# USB_DVI.net
KiCad netlist of a schematic drawn in Altium Designer
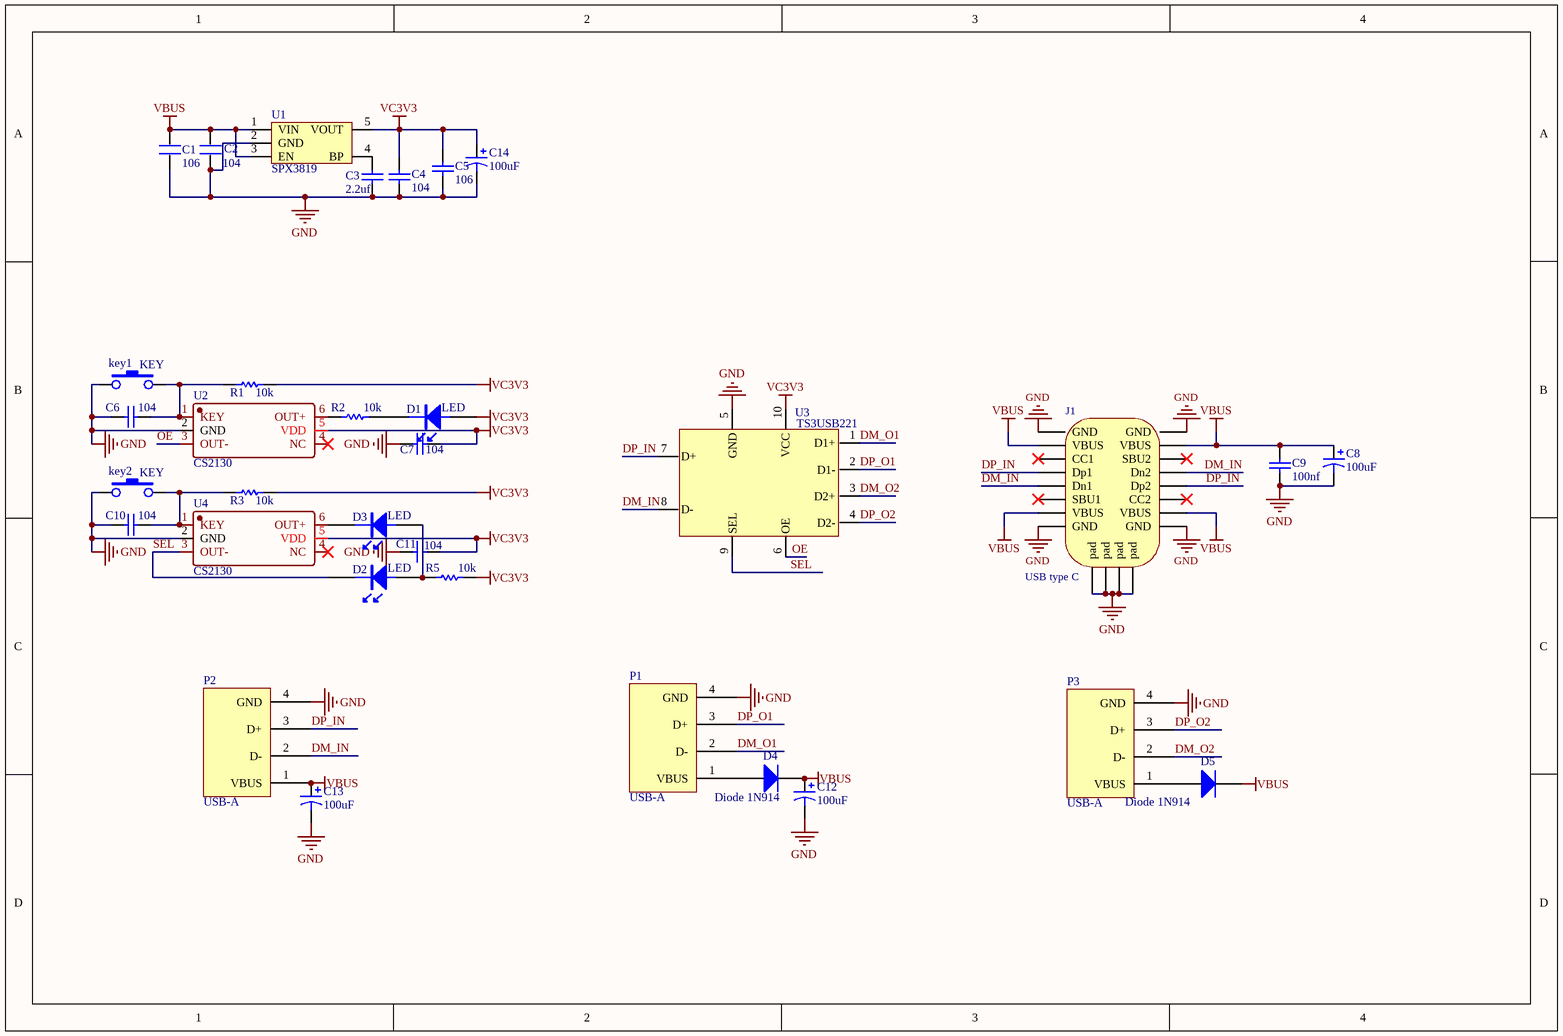
[diagram p0: USB_DVI.SchDoc]

(export (version "E")
  (design (tool "Eeschema 10.0.6"))
  (components
    (comp (ref "C1") (value "106") (footprint "C 0603") (libsource (lib "Mlia") (part "0603C")))
    (comp (ref "C2") (value "104") (footprint "C 0603") (libsource (lib "Mlia") (part "0603C")))
    (comp (ref "C3")
      (value "2.2uf")
      (footprint "C 0603")
      (description "Polarized Capacitor (Radial)")
      (fields (field (name "Comment") "Cap") (field (name "PUBLISHER") "Altium Limited"))
      (libsource (lib "Fantasy") (part "Cap"))
    )
    (comp (ref "C4")
      (value "104")
      (footprint "C 0603")
      (description "Polarized Capacitor (Radial)")
      (fields (field (name "Comment") "Cap") (field (name "PUBLISHER") "Altium Limited"))
      (libsource (lib "Fantasy") (part "Cap"))
    )
    (comp (ref "C5")
      (value "106")
      (footprint "C 0603")
      (description "Polarized Capacitor (Radial)")
      (fields (field (name "Comment") "Cap") (field (name "PUBLISHER") "Altium Limited"))
      (libsource (lib "Fantasy") (part "Cap"))
    )
    (comp (ref "C6")
      (value "104")
      (footprint "C 0603")
      (description "Polarized Capacitor (Radial)")
      (fields (field (name "Comment") "Cap") (field (name "PUBLISHER") "Altium Limited"))
      (libsource (lib "Fantasy") (part "Cap"))
    )
    (comp (ref "C7")
      (value "104")
      (footprint "C 0603")
      (description "Polarized Capacitor (Radial)")
      (fields (field (name "Comment") "Cap") (field (name "PUBLISHER") "Altium Limited"))
      (libsource (lib "Fantasy") (part "Cap"))
    )
    (comp (ref "C8")
      (value "100uF")
      (footprint "C 1210")
      (description "贴片电解电容")
      (fields (field (name "PUBLISHER") "Altium Limited"))
      (libsource (lib "Miscellaneous Devices") (part "Cap Pol1"))
    )
    (comp (ref "C9")
      (value "100nf")
      (footprint "C 0603")
      (description "贴片电容")
      (fields (field (name "PUBLISHER") "Altium Limited"))
      (libsource (lib "Miscellaneous Devices") (part "Cap"))
    )
    (comp (ref "C10")
      (value "104")
      (footprint "C 0603")
      (description "Polarized Capacitor (Radial)")
      (fields (field (name "Comment") "Cap") (field (name "PUBLISHER") "Altium Limited"))
      (libsource (lib "Fantasy") (part "Cap"))
    )
    (comp (ref "C11")
      (value "104")
      (footprint "C 0603")
      (description "Polarized Capacitor (Radial)")
      (fields (field (name "Comment") "Cap") (field (name "PUBLISHER") "Altium Limited"))
      (libsource (lib "Fantasy") (part "Cap"))
    )
    (comp (ref "C12")
      (value "100uF")
      (footprint "C 1210")
      (description "贴片电解电容")
      (fields (field (name "PUBLISHER") "Altium Limited"))
      (libsource (lib "Miscellaneous Devices") (part "Cap Pol1"))
    )
    (comp (ref "C13")
      (value "100uF")
      (footprint "C 1210")
      (description "贴片电解电容")
      (fields (field (name "PUBLISHER") "Altium Limited"))
      (libsource (lib "Miscellaneous Devices") (part "Cap Pol1"))
    )
    (comp (ref "C14")
      (value "100uF")
      (footprint "C 1210")
      (description "贴片电解电容")
      (fields (field (name "PUBLISHER") "Altium Limited"))
      (libsource (lib "Miscellaneous Devices") (part "Cap Pol1"))
    )
    (comp (ref "D1") (value "LED") (footprint "LED 0603B") (libsource (lib "STM32F103C8T6") (part "LED")))
    (comp (ref "D2") (value "LED") (footprint "LED 0603B") (libsource (lib "STM32F103C8T6") (part "LED")))
    (comp (ref "D3") (value "LED") (footprint "LED 0603B") (libsource (lib "STM32F103C8T6") (part "LED")))
    (comp (ref "D4")
      (value "Diode 1N914")
      (footprint "SOD-323")
      (description "High Conductance Fast Diode")
      (fields (field (name "PUBLISHER") "Altium Limited"))
      (libsource (lib "LONG_lclr") (part "Diode 1N914"))
    )
    (comp (ref "D5")
      (value "Diode 1N914")
      (footprint "SOD-323")
      (description "High Conductance Fast Diode")
      (fields (field (name "PUBLISHER") "Altium Limited"))
      (libsource (lib "LONG_lclr") (part "Diode 1N914"))
    )
    (comp (ref "J1")
      (value "USB type C")
      (footprint "TYPEC_D")
      (description "USB type C 16P")
      (libsource (lib "altium-import") (part "root_0_USB type C_"))
    )
    (comp (ref "key1") (value "KEY") (footprint "KEY - duplicate") (libsource (lib "LONG_lclr") (part "KEY")))
    (comp (ref "key2") (value "KEY") (footprint "KEY - duplicate") (libsource (lib "LONG_lclr") (part "KEY")))
    (comp (ref "P1") (value "USB-A") (footprint "USB-A") (libsource (lib "MyPcbLib") (part "USB-A")))
    (comp (ref "P2") (value "USB-A") (footprint "USB-A") (libsource (lib "MyPcbLib") (part "USB-A")))
    (comp (ref "P3") (value "USB-A") (footprint "USB-A") (libsource (lib "MyPcbLib") (part "USB-A")))
    (comp (ref "R1")
      (value "10k")
      (footprint "R 0603")
      (description "贴片电阻")
      (fields (field (name "PUBLISHER") "Altium Limited"))
      (libsource (lib "Miscellaneous Devices") (part "Res1"))
    )
    (comp (ref "R2")
      (value "10k")
      (footprint "R 0603")
      (description "贴片电阻")
      (fields (field (name "PUBLISHER") "Altium Limited"))
      (libsource (lib "Miscellaneous Devices") (part "Res1"))
    )
    (comp (ref "R3")
      (value "10k")
      (footprint "R 0603")
      (description "贴片电阻")
      (fields (field (name "PUBLISHER") "Altium Limited"))
      (libsource (lib "Miscellaneous Devices") (part "Res1"))
    )
    (comp (ref "R5")
      (value "10k")
      (footprint "R 0603")
      (description "贴片电阻")
      (fields (field (name "PUBLISHER") "Altium Limited"))
      (libsource (lib "Miscellaneous Devices") (part "Res1"))
    )
    (comp (ref "U1")
      (value "SPX3819")
      (footprint "SOT23-5N")
      (description "3.3V超低压差LDO")
      (libsource (lib "Fantasy") (part "RT9193-33"))
    )
    (comp (ref "U2") (value "CS2130") (footprint "SOT23-6L") (libsource (lib "LONG_lclr") (part "CS2130")))
    (comp (ref "U3")
      (value "TS3USB221")
      (footprint "UQFN-10_L2.0-W1.5-P0.50-BL")
      (libsource (lib "LONG_lclr") (part "TS3USB221"))
    )
    (comp (ref "U4") (value "CS2130") (footprint "SOT23-6L") (libsource (lib "LONG_lclr") (part "CS2130")))
  )
  (nets
    (net (code "1") (name "/DM_IN") (class "Default")
      (node (ref "J1") (pin "A7") (pinfunction "Dn1_A7") (pintype "passive"))
      (node (ref "J1") (pin "B7") (pinfunction "Dn2_B7") (pintype "passive"))
      (node (ref "P2") (pin "2") (pinfunction "D-_2") (pintype "passive"))
      (node (ref "U3") (pin "8") (pinfunction "D-_8") (pintype "passive"))
    )
    (net (code "2") (name "/DM_O1") (class "Default")
      (node (ref "P1") (pin "2") (pinfunction "D-_2") (pintype "passive"))
      (node (ref "U3") (pin "1") (pinfunction "D1+_1") (pintype "passive"))
    )
    (net (code "3") (name "/DM_O2") (class "Default")
      (node (ref "P3") (pin "2") (pinfunction "D-_2") (pintype "passive"))
      (node (ref "U3") (pin "3") (pinfunction "D2+_3") (pintype "passive"))
    )
    (net (code "4") (name "/DP_IN") (class "Default")
      (node (ref "J1") (pin "A6") (pinfunction "Dp1_A6") (pintype "passive"))
      (node (ref "J1") (pin "B6") (pinfunction "Dp2_B6") (pintype "passive"))
      (node (ref "P2") (pin "3") (pinfunction "D+_3") (pintype "passive"))
      (node (ref "U3") (pin "7") (pinfunction "D+_7") (pintype "passive"))
    )
    (net (code "5") (name "/DP_O1") (class "Default")
      (node (ref "P1") (pin "3") (pinfunction "D+_3") (pintype "passive"))
      (node (ref "U3") (pin "2") (pinfunction "D1-_2") (pintype "passive"))
    )
    (net (code "6") (name "/DP_O2") (class "Default")
      (node (ref "P3") (pin "3") (pinfunction "D+_3") (pintype "passive"))
      (node (ref "U3") (pin "4") (pinfunction "D2-_4") (pintype "passive"))
    )
    (net (code "7") (name "/OE") (class "Default")
      (node (ref "U2") (pin "3") (pinfunction "OUT-_3") (pintype "passive"))
      (node (ref "U3") (pin "6") (pinfunction "OE_6") (pintype "passive"))
    )
    (net (code "8") (name "/SEL") (class "Default")
      (node (ref "D2") (pin "2") (pinfunction "2_2") (pintype "passive"))
      (node (ref "U3") (pin "9") (pinfunction "SEL_9") (pintype "passive"))
      (node (ref "U4") (pin "3") (pinfunction "OUT-_3") (pintype "passive"))
    )
    (net (code "9") (name "GND") (class "Default")
      (node (ref "C1") (pin "1") (pintype "passive"))
      (node (ref "C10") (pin "2") (pinfunction "2_2") (pintype "passive"))
      (node (ref "C11") (pin "2") (pinfunction "2_2") (pintype "passive"))
      (node (ref "C12") (pin "2") (pinfunction "2_2") (pintype "passive"))
      (node (ref "C13") (pin "2") (pinfunction "2_2") (pintype "passive"))
      (node (ref "C14") (pin "2") (pinfunction "2_2") (pintype "passive"))
      (node (ref "C2") (pin "1") (pintype "passive"))
      (node (ref "C3") (pin "1") (pinfunction "1_1") (pintype "passive"))
      (node (ref "C4") (pin "1") (pinfunction "1_1") (pintype "passive"))
      (node (ref "C5") (pin "1") (pinfunction "1_1") (pintype "passive"))
      (node (ref "C6") (pin "2") (pinfunction "2_2") (pintype "passive"))
      (node (ref "C7") (pin "2") (pinfunction "2_2") (pintype "passive"))
      (node (ref "C8") (pin "2") (pinfunction "2_2") (pintype "passive"))
      (node (ref "C9") (pin "2") (pinfunction "2_2") (pintype "passive"))
      (node (ref "J1") (pin "1") (pinfunction "pad_1") (pintype "passive"))
      (node (ref "J1") (pin "A1") (pinfunction "GND_A1") (pintype "passive"))
      (node (ref "J1") (pin "A12") (pinfunction "GND_A12") (pintype "passive"))
      (node (ref "J1") (pin "B1") (pinfunction "GND_B1") (pintype "passive"))
      (node (ref "J1") (pin "B12") (pinfunction "GND_B12") (pintype "passive"))
      (node (ref "P1") (pin "4") (pinfunction "GND_4") (pintype "passive"))
      (node (ref "P2") (pin "4") (pinfunction "GND_4") (pintype "passive"))
      (node (ref "P3") (pin "4") (pinfunction "GND_4") (pintype "passive"))
      (node (ref "U1") (pin "2") (pinfunction "GND_2") (pintype "passive"))
      (node (ref "U2") (pin "2") (pinfunction "GND_2") (pintype "passive"))
      (node (ref "U3") (pin "5") (pinfunction "GND_5") (pintype "passive"))
      (node (ref "U4") (pin "2") (pinfunction "GND_2") (pintype "passive"))
      (node (ref "key1") (pin "1") (pinfunction "1_1") (pintype "passive"))
      (node (ref "key2") (pin "1") (pinfunction "1_1") (pintype "passive"))
    )
    (net (code "10") (name "Net-(D1-Pad2)") (class "Default")
      (node (ref "D1") (pin "2") (pinfunction "2_2") (pintype "passive"))
      (node (ref "R2") (pin "1") (pinfunction "1_1") (pintype "passive"))
    )
    (net (code "11") (name "Net-(D2-Pad1)") (class "Default")
      (node (ref "D2") (pin "1") (pinfunction "1_1") (pintype "passive"))
      (node (ref "D3") (pin "1") (pinfunction "1_1") (pintype "passive"))
      (node (ref "R5") (pin "2") (pinfunction "2_2") (pintype "passive"))
    )
    (net (code "12") (name "Net-(D4-A)") (class "Default")
      (node (ref "D4") (pin "1") (pinfunction "A_1") (pintype "passive"))
      (node (ref "P1") (pin "1") (pinfunction "VBUS_1") (pintype "passive"))
    )
    (net (code "13") (name "Net-(D5-A)") (class "Default")
      (node (ref "D5") (pin "1") (pinfunction "A_1") (pintype "passive"))
      (node (ref "P3") (pin "1") (pinfunction "VBUS_1") (pintype "passive"))
    )
    (net (code "14") (name "Net-(U1-BP)") (class "Default")
      (node (ref "C3") (pin "2") (pinfunction "2_2") (pintype "passive"))
      (node (ref "U1") (pin "4") (pinfunction "BP_4") (pintype "passive"))
    )
    (net (code "15") (name "Net-(U2-KEY)") (class "Default")
      (node (ref "C6") (pin "1") (pinfunction "1_1") (pintype "passive"))
      (node (ref "R1") (pin "2") (pinfunction "2_2") (pintype "passive"))
      (node (ref "U2") (pin "1") (pinfunction "KEY_1") (pintype "passive"))
      (node (ref "key1") (pin "2") (pinfunction "2_2") (pintype "passive"))
    )
    (net (code "16") (name "Net-(U2-OUT+)") (class "Default")
      (node (ref "R2") (pin "2") (pinfunction "2_2") (pintype "passive"))
      (node (ref "U2") (pin "6") (pinfunction "OUT+_6") (pintype "passive"))
    )
    (net (code "17") (name "Net-(U4-KEY)") (class "Default")
      (node (ref "C10") (pin "1") (pinfunction "1_1") (pintype "passive"))
      (node (ref "R3") (pin "2") (pinfunction "2_2") (pintype "passive"))
      (node (ref "U4") (pin "1") (pinfunction "KEY_1") (pintype "passive"))
      (node (ref "key2") (pin "2") (pinfunction "2_2") (pintype "passive"))
    )
    (net (code "18") (name "Net-(U4-OUT+)") (class "Default")
      (node (ref "D3") (pin "2") (pinfunction "2_2") (pintype "passive"))
      (node (ref "U4") (pin "6") (pinfunction "OUT+_6") (pintype "passive"))
    )
    (net (code "19") (name "VBUS") (class "Default")
      (node (ref "C1") (pin "2") (pintype "passive"))
      (node (ref "C12") (pin "1") (pinfunction "1_1") (pintype "passive"))
      (node (ref "C13") (pin "1") (pinfunction "1_1") (pintype "passive"))
      (node (ref "C2") (pin "2") (pintype "passive"))
      (node (ref "C8") (pin "1") (pinfunction "1_1") (pintype "passive"))
      (node (ref "C9") (pin "1") (pinfunction "1_1") (pintype "passive"))
      (node (ref "D4") (pin "2") (pinfunction "K_2") (pintype "passive"))
      (node (ref "D5") (pin "2") (pinfunction "K_2") (pintype "passive"))
      (node (ref "J1") (pin "A4") (pinfunction "VBUS_A4") (pintype "passive"))
      (node (ref "J1") (pin "A9") (pinfunction "VBUS_A9") (pintype "passive"))
      (node (ref "J1") (pin "B4") (pinfunction "VBUS_B4") (pintype "passive"))
      (node (ref "J1") (pin "B9") (pinfunction "VBUS_B9") (pintype "passive"))
      (node (ref "P2") (pin "1") (pinfunction "VBUS_1") (pintype "passive"))
      (node (ref "U1") (pin "1") (pinfunction "VIN_1") (pintype "passive"))
      (node (ref "U1") (pin "3") (pinfunction "EN_3") (pintype "passive"))
    )
    (net (code "20") (name "VC3V3") (class "Default")
      (node (ref "C11") (pin "1") (pinfunction "1_1") (pintype "passive"))
      (node (ref "C14") (pin "1") (pinfunction "1_1") (pintype "passive"))
      (node (ref "C4") (pin "2") (pinfunction "2_2") (pintype "passive"))
      (node (ref "C5") (pin "2") (pinfunction "2_2") (pintype "passive"))
      (node (ref "C7") (pin "1") (pinfunction "1_1") (pintype "passive"))
      (node (ref "D1") (pin "1") (pinfunction "1_1") (pintype "passive"))
      (node (ref "R1") (pin "1") (pinfunction "1_1") (pintype "passive"))
      (node (ref "R3") (pin "1") (pinfunction "1_1") (pintype "passive"))
      (node (ref "R5") (pin "1") (pinfunction "1_1") (pintype "passive"))
      (node (ref "U1") (pin "5") (pinfunction "VOUT_5") (pintype "passive"))
      (node (ref "U2") (pin "5") (pinfunction "VDD_5") (pintype "passive"))
      (node (ref "U3") (pin "10") (pinfunction "VCC_10") (pintype "passive"))
      (node (ref "U4") (pin "5") (pinfunction "VDD_5") (pintype "passive"))
    )
    (net (code "21") (name "unconnected-(J1-CC1-PadA5)") (class "Default")
      (node (ref "J1") (pin "A5") (pinfunction "CC1_A5") (pintype "passive+no_connect"))
    )
    (net (code "22") (name "unconnected-(J1-CC2-PadB5)") (class "Default")
      (node (ref "J1") (pin "B5") (pinfunction "CC2_B5") (pintype "passive+no_connect"))
    )
    (net (code "23") (name "unconnected-(J1-SBU1-PadA8)") (class "Default")
      (node (ref "J1") (pin "A8") (pinfunction "SBU1_A8") (pintype "passive+no_connect"))
    )
    (net (code "24") (name "unconnected-(J1-SBU2-PadB8)") (class "Default")
      (node (ref "J1") (pin "B8") (pinfunction "SBU2_B8") (pintype "passive+no_connect"))
    )
    (net (code "25") (name "unconnected-(U2-NC-Pad4)") (class "Default")
      (node (ref "U2") (pin "4") (pinfunction "NC_4") (pintype "passive+no_connect"))
    )
    (net (code "26") (name "unconnected-(U4-NC-Pad4)") (class "Default")
      (node (ref "U4") (pin "4") (pinfunction "NC_4") (pintype "passive+no_connect"))
    )
  )
)
